# 1LD-15-mk-1_0.net
KiCad netlist of a schematic drawn in EAGLE
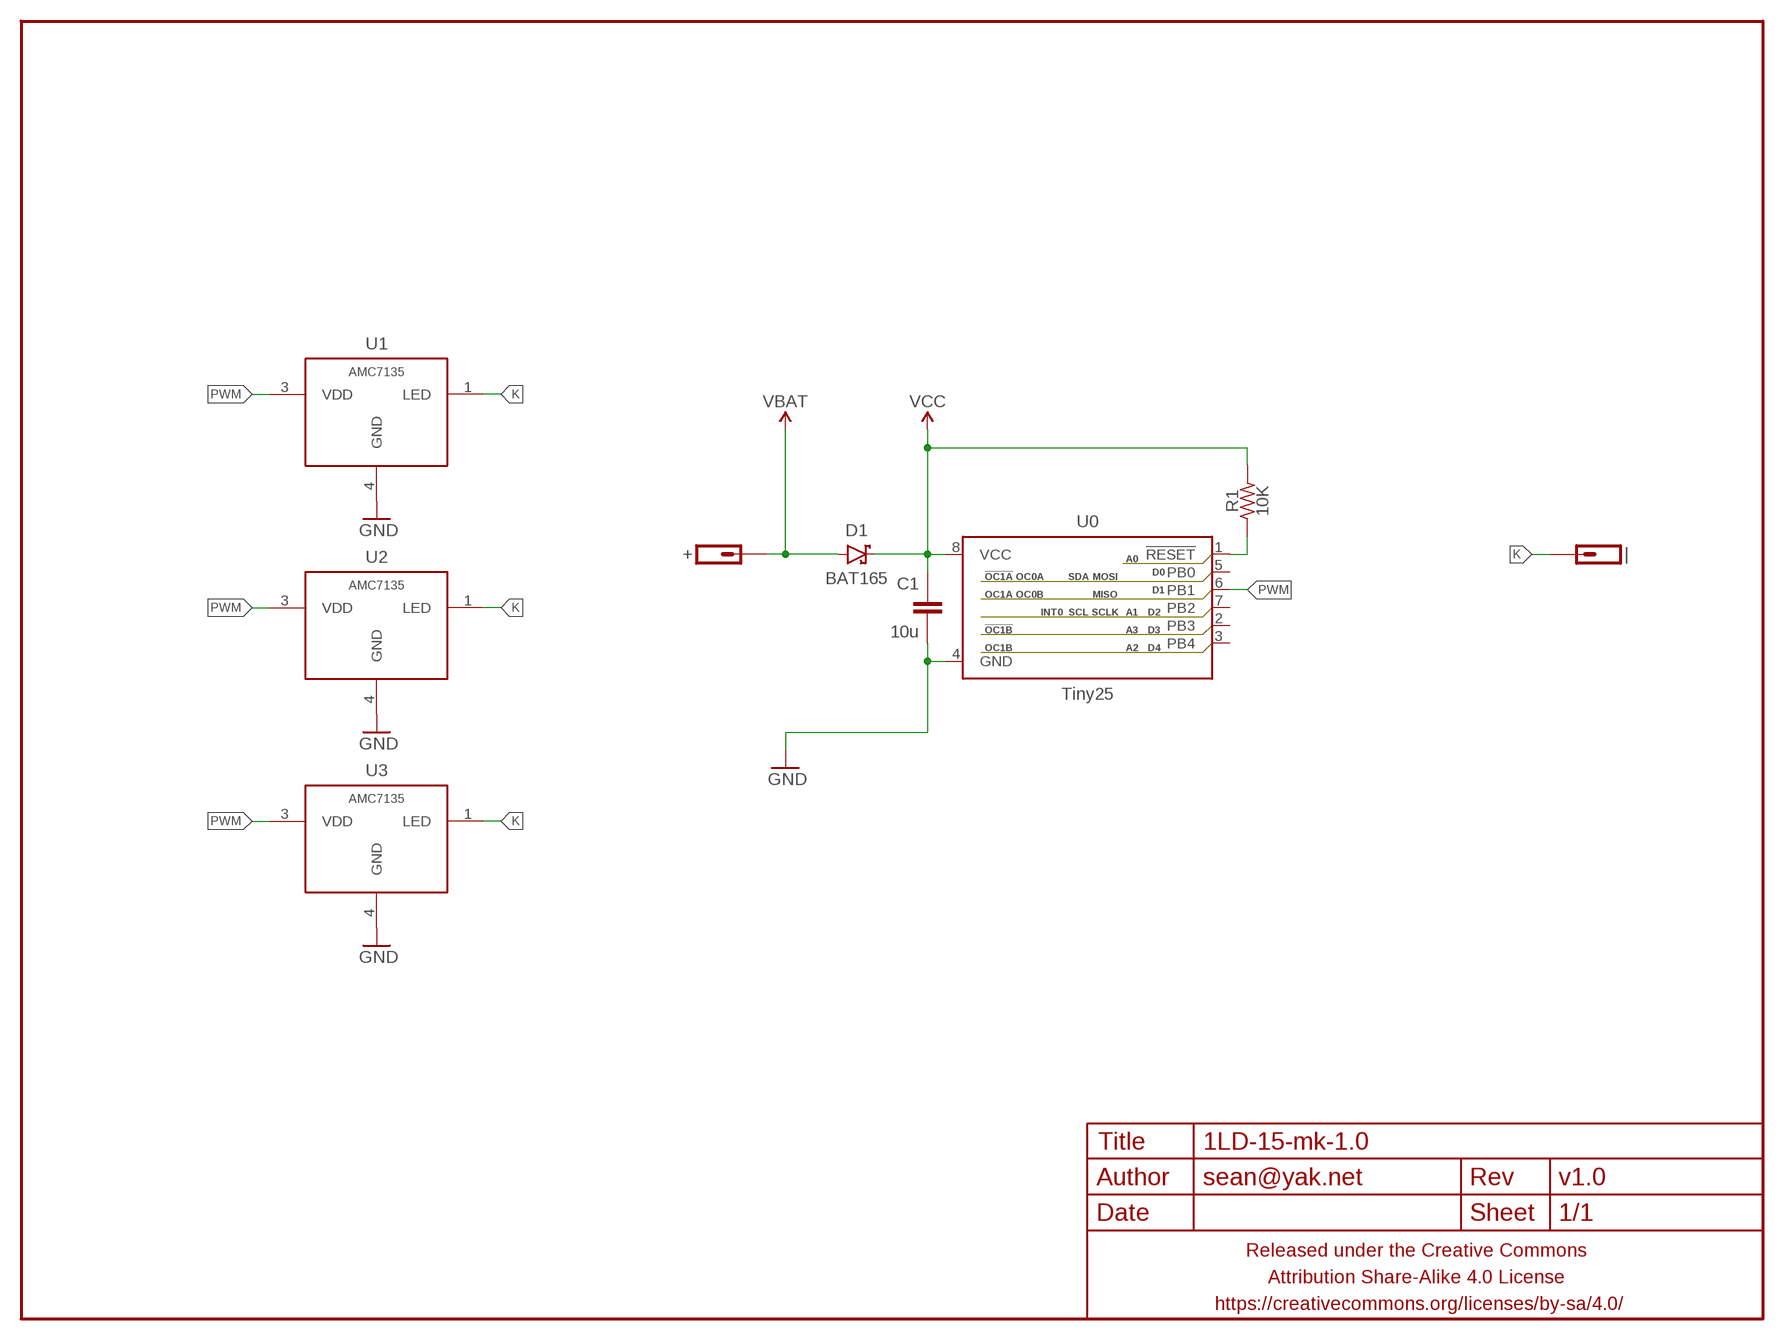
[diagram p0: schematic, sheet 1]

(export (version "E")
  (design (tool "Eeschema 10.0.6"))
  (components
    (comp (ref "+")
      (value "M01PTH-0.8MM-CIR")
      (footprint "eagle-import:1X01-0.8MM-CIR")
      (libsource (lib "eagle-import") (part "M01PTH-0.8MM-CIR"))
    )
    (comp (ref "C1")
      (value "10u")
      (footprint "eagle-import:C0603-TIGHTER")
      (libsource (lib "eagle-import") (part "CAPACITOR-CERAMICC0603-TIGHTER"))
    )
    (comp (ref "D1")
      (value "BAT165")
      (footprint "eagle-import:SOD-123-SCHOTTYK-ROUND")
      (libsource (lib "eagle-import") (part "DIODE-SCHOTTKYSOD123-ROUNDED"))
    )
    (comp (ref "FRAME1")
      (value "FRAME-LETTERNO_PACKAGE")
      (footprint "eagle-import:DUMMY")
      (fields (field (name "DESIGNER") "sean@yak.net") (field (name "VERSION") "v1.0"))
      (libsource (lib "eagle-import") (part "FRAME-LETTERNO_PACKAGE"))
    )
    (comp (ref "R1")
      (value "10K")
      (footprint "eagle-import:R0603-TIGHTER")
      (libsource (lib "eagle-import") (part "RESISTORR0603-TIGHTER"))
    )
    (comp (ref "U0")
      (value "Tiny25")
      (footprint "eagle-import:SO08-NARROWER")
      (libsource (lib "eagle-import") (part "ATTINY13SOIC-NARROWPADS"))
    )
    (comp (ref "U1")
      (value "AMC7135")
      (footprint "eagle-import:SOT89-NOTHERM-ROUNDED-LESS")
      (libsource (lib "eagle-import") (part "AMC7135SOT-89-NOTHERM-ROUNDED-LESS"))
    )
    (comp (ref "U2")
      (value "AMC7135")
      (footprint "eagle-import:SOT89-NOTHERM-ROUNDED-LESS")
      (libsource (lib "eagle-import") (part "AMC7135SOT-89-NOTHERM-ROUNDED-LESS"))
    )
    (comp (ref "U3")
      (value "AMC7135")
      (footprint "eagle-import:SOT89-NOTHERM-ROUNDED-LESS")
      (libsource (lib "eagle-import") (part "AMC7135SOT-89-NOTHERM-ROUNDED-LESS"))
    )
    (comp (ref "|")
      (value "M01PTH-0.8MM-CIR")
      (footprint "eagle-import:1X01-0.8MM-CIR")
      (libsource (lib "eagle-import") (part "M01PTH-0.8MM-CIR"))
    )
  )
  (nets
    (net (code "1") (name "GND") (class "Default")
      (node (ref "C1") (pin "2") (pinfunction "2_2") (pintype "passive"))
      (node (ref "U0") (pin "4") (pinfunction "GND_4") (pintype "bidirectional"))
      (node (ref "U1") (pin "4") (pinfunction "GND_4") (pintype "bidirectional"))
      (node (ref "U2") (pin "4") (pinfunction "GND_4") (pintype "bidirectional"))
      (node (ref "U3") (pin "4") (pinfunction "GND_4") (pintype "bidirectional"))
    )
    (net (code "2") (name "K") (class "Default")
      (node (ref "U1") (pin "1") (pinfunction "LED_1") (pintype "bidirectional"))
      (node (ref "U2") (pin "1") (pinfunction "LED_1") (pintype "bidirectional"))
      (node (ref "U3") (pin "1") (pinfunction "LED_1") (pintype "bidirectional"))
      (node (ref "|") (pin "1") (pinfunction "1_1") (pintype "passive"))
    )
    (net (code "3") (name "Net-(U0-~{RESET})") (class "Default")
      (node (ref "R1") (pin "1") (pinfunction "1_1") (pintype "passive"))
      (node (ref "U0") (pin "1") (pinfunction "~{RESET}_1") (pintype "bidirectional"))
    )
    (net (code "4") (name "PWM") (class "Default")
      (node (ref "U0") (pin "6") (pinfunction "PB1_6") (pintype "bidirectional"))
      (node (ref "U1") (pin "3") (pinfunction "VDD_3") (pintype "bidirectional"))
      (node (ref "U2") (pin "3") (pinfunction "VDD_3") (pintype "bidirectional"))
      (node (ref "U3") (pin "3") (pinfunction "VDD_3") (pintype "bidirectional"))
    )
    (net (code "5") (name "VBAT") (class "Default")
      (node (ref "+") (pin "1") (pinfunction "1_1") (pintype "passive"))
      (node (ref "D1") (pin "A") (pinfunction "A_A") (pintype "passive"))
    )
    (net (code "6") (name "VCC") (class "Default")
      (node (ref "C1") (pin "1") (pinfunction "1_1") (pintype "passive"))
      (node (ref "D1") (pin "C") (pinfunction "C_C") (pintype "passive"))
      (node (ref "R1") (pin "2") (pinfunction "2_2") (pintype "passive"))
      (node (ref "U0") (pin "8") (pinfunction "VCC_8") (pintype "bidirectional"))
    )
    (net (code "7") (name "unconnected-(U0-PB0-Pad5)") (class "Default")
      (node (ref "U0") (pin "5") (pinfunction "PB0_5") (pintype "bidirectional"))
    )
    (net (code "8") (name "unconnected-(U0-PB2-Pad7)") (class "Default")
      (node (ref "U0") (pin "7") (pinfunction "PB2_7") (pintype "bidirectional"))
    )
    (net (code "9") (name "unconnected-(U0-PB3-Pad2)") (class "Default")
      (node (ref "U0") (pin "2") (pinfunction "PB3_2") (pintype "bidirectional"))
    )
    (net (code "10") (name "unconnected-(U0-PB4-Pad3)") (class "Default")
      (node (ref "U0") (pin "3") (pinfunction "PB4_3") (pintype "bidirectional"))
    )
  )
)
